# TUDSSL_condenar__Hardware_PCBs_Logger_Sc.net
KiCad netlist of a schematic drawn in Altium Designer
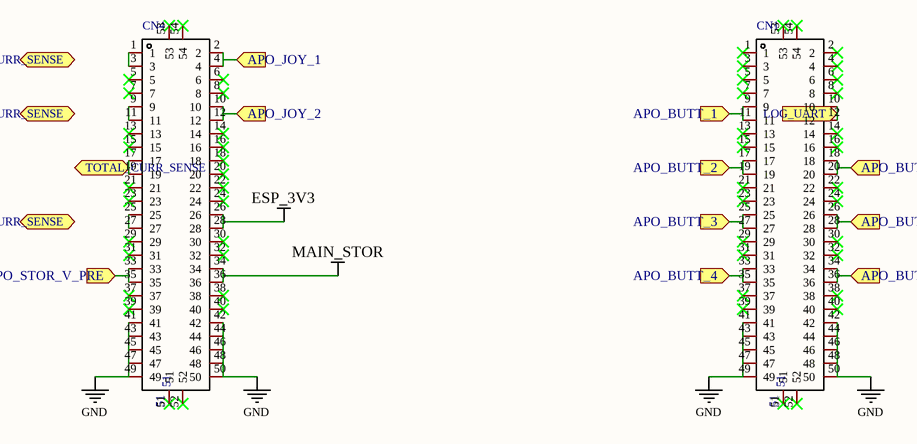
[diagram p0: TUDSSL_condenar__Hardware_PCBs_Logger_Schematic2__1_Connector.schdoc]

(export (version "E")
  (design (tool "Eeschema 10.0.6"))
  (components
    (comp (ref "CN1")
      (value "DF40C-50DP-0.4V(51)")
      (fields (field (name "MANUFACTURER") "HRS(广濑)") (field (name "NAME") "51") (field (name "NUMBER") "51"))
      (libsource (lib "altium-import") (part "root_0_DF40C-50DP-0.4V(51)_"))
    )
    (comp (ref "CN4")
      (value "DF40C-50DP-0.4V(51)")
      (fields (field (name "MANUFACTURER") "HRS(广濑)") (field (name "NAME") "51") (field (name "NUMBER") "51"))
      (libsource (lib "altium-import") (part "root_0_DF40C-50DP-0.4V(51)_"))
    )
  )
  (nets
    (net (code "1") (name "/APO_BUTT_1") (class "Default")
      (node (ref "CN1") (pin "11") (pinfunction "11_11") (pintype "passive"))
      (node (ref "CN1") (pin "9") (pinfunction "9_9") (pintype "passive"))
    )
    (net (code "2") (name "/APO_BUTT_2") (class "Default")
      (node (ref "CN1") (pin "17") (pinfunction "17_17") (pintype "passive"))
      (node (ref "CN1") (pin "19") (pinfunction "19_19") (pintype "passive"))
    )
    (net (code "3") (name "/APO_BUTT_3") (class "Default")
      (node (ref "CN1") (pin "25") (pinfunction "25_25") (pintype "passive"))
      (node (ref "CN1") (pin "27") (pinfunction "27_27") (pintype "passive"))
    )
    (net (code "4") (name "/APO_BUTT_4") (class "Default")
      (node (ref "CN1") (pin "33") (pinfunction "33_33") (pintype "passive"))
      (node (ref "CN1") (pin "35") (pinfunction "35_35") (pintype "passive"))
    )
    (net (code "5") (name "/APO_BUTT_5") (class "Default")
      (node (ref "CN1") (pin "34") (pinfunction "34_34") (pintype "passive"))
      (node (ref "CN1") (pin "36") (pinfunction "36_36") (pintype "passive"))
    )
    (net (code "6") (name "/APO_BUTT_6") (class "Default")
      (node (ref "CN1") (pin "26") (pinfunction "26_26") (pintype "passive"))
      (node (ref "CN1") (pin "28") (pinfunction "28_28") (pintype "passive"))
    )
    (net (code "7") (name "/APO_BUTT_7") (class "Default")
      (node (ref "CN1") (pin "18") (pinfunction "18_18") (pintype "passive"))
      (node (ref "CN1") (pin "20") (pinfunction "20_20") (pintype "passive"))
    )
    (net (code "8") (name "/APO_JOY_1") (class "Default")
      (node (ref "CN4") (pin "2") (pinfunction "2_2") (pintype "passive"))
      (node (ref "CN4") (pin "4") (pinfunction "4_4") (pintype "passive"))
    )
    (net (code "9") (name "/APO_JOY_2") (class "Default")
      (node (ref "CN4") (pin "10") (pinfunction "10_10") (pintype "passive"))
      (node (ref "CN4") (pin "12") (pinfunction "12_12") (pintype "passive"))
    )
    (net (code "10") (name "/APO_STOR_V_PRE") (class "Default")
      (node (ref "CN4") (pin "33") (pinfunction "33_33") (pintype "passive"))
      (node (ref "CN4") (pin "35") (pinfunction "35_35") (pintype "passive"))
    )
    (net (code "13") (name "/LOG_UART") (class "Default")
      (node (ref "CN1") (pin "10") (pinfunction "10_10") (pintype "passive"))
      (node (ref "CN1") (pin "12") (pinfunction "12_12") (pintype "passive"))
    )
    (net (code "16") (name "ESP_3V3") (class "Default")
      (node (ref "CN4") (pin "26") (pinfunction "26_26") (pintype "passive"))
      (node (ref "CN4") (pin "28") (pinfunction "28_28") (pintype "passive"))
    )
    (net (code "17") (name "GND") (class "Default")
      (node (ref "CN1") (pin "41") (pinfunction "41_41") (pintype "passive"))
      (node (ref "CN1") (pin "42") (pinfunction "42_42") (pintype "passive"))
      (node (ref "CN1") (pin "43") (pinfunction "43_43") (pintype "passive"))
      (node (ref "CN1") (pin "44") (pinfunction "44_44") (pintype "passive"))
      (node (ref "CN1") (pin "45") (pinfunction "45_45") (pintype "passive"))
      (node (ref "CN1") (pin "46") (pinfunction "46_46") (pintype "passive"))
      (node (ref "CN1") (pin "47") (pinfunction "47_47") (pintype "passive"))
      (node (ref "CN1") (pin "48") (pinfunction "48_48") (pintype "passive"))
      (node (ref "CN1") (pin "49") (pinfunction "49_49") (pintype "passive"))
      (node (ref "CN1") (pin "50") (pinfunction "50_50") (pintype "passive"))
      (node (ref "CN4") (pin "41") (pinfunction "41_41") (pintype "passive"))
      (node (ref "CN4") (pin "42") (pinfunction "42_42") (pintype "passive"))
      (node (ref "CN4") (pin "43") (pinfunction "43_43") (pintype "passive"))
      (node (ref "CN4") (pin "44") (pinfunction "44_44") (pintype "passive"))
      (node (ref "CN4") (pin "45") (pinfunction "45_45") (pintype "passive"))
      (node (ref "CN4") (pin "46") (pinfunction "46_46") (pintype "passive"))
      (node (ref "CN4") (pin "47") (pinfunction "47_47") (pintype "passive"))
      (node (ref "CN4") (pin "48") (pinfunction "48_48") (pintype "passive"))
      (node (ref "CN4") (pin "49") (pinfunction "49_49") (pintype "passive"))
      (node (ref "CN4") (pin "50") (pinfunction "50_50") (pintype "passive"))
    )
    (net (code "18") (name "MAIN_STOR") (class "Default")
      (node (ref "CN4") (pin "34") (pinfunction "34_34") (pintype "passive"))
      (node (ref "CN4") (pin "36") (pinfunction "36_36") (pintype "passive"))
    )
    (net (code "19") (name "Net-(CN4-Pad1)") (class "Default")
      (node (ref "CN4") (pin "1") (pinfunction "1_1") (pintype "passive"))
      (node (ref "CN4") (pin "3") (pinfunction "3_3") (pintype "passive"))
    )
    (net (code "20") (name "Net-(CN4-Pad11)") (class "Default")
      (node (ref "CN4") (pin "11") (pinfunction "11_11") (pintype "passive"))
      (node (ref "CN4") (pin "9") (pinfunction "9_9") (pintype "passive"))
    )
    (net (code "21") (name "Net-(CN4-Pad17)") (class "Default")
      (node (ref "CN4") (pin "17") (pinfunction "17_17") (pintype "passive"))
      (node (ref "CN4") (pin "19") (pinfunction "19_19") (pintype "passive"))
    )
    (net (code "22") (name "Net-(CN4-Pad25)") (class "Default")
      (node (ref "CN4") (pin "25") (pinfunction "25_25") (pintype "passive"))
      (node (ref "CN4") (pin "27") (pinfunction "27_27") (pintype "passive"))
    )
    (net (code "23") (name "unconnected-(CN1-Pad1)") (class "Default")
      (node (ref "CN1") (pin "1") (pinfunction "1_1") (pintype "passive+no_connect"))
    )
    (net (code "24") (name "unconnected-(CN1-Pad2)") (class "Default")
      (node (ref "CN1") (pin "2") (pinfunction "2_2") (pintype "passive+no_connect"))
    )
    (net (code "25") (name "unconnected-(CN1-Pad3)") (class "Default")
      (node (ref "CN1") (pin "3") (pinfunction "3_3") (pintype "passive+no_connect"))
    )
    (net (code "26") (name "unconnected-(CN1-Pad4)") (class "Default")
      (node (ref "CN1") (pin "4") (pinfunction "4_4") (pintype "passive+no_connect"))
    )
    (net (code "27") (name "unconnected-(CN1-Pad5)") (class "Default")
      (node (ref "CN1") (pin "5") (pinfunction "5_5") (pintype "passive+no_connect"))
    )
    (net (code "28") (name "unconnected-(CN1-Pad6)") (class "Default")
      (node (ref "CN1") (pin "6") (pinfunction "6_6") (pintype "passive+no_connect"))
    )
    (net (code "29") (name "unconnected-(CN1-Pad7)") (class "Default")
      (node (ref "CN1") (pin "7") (pinfunction "7_7") (pintype "passive+no_connect"))
    )
    (net (code "30") (name "unconnected-(CN1-Pad8)") (class "Default")
      (node (ref "CN1") (pin "8") (pinfunction "8_8") (pintype "passive+no_connect"))
    )
    (net (code "31") (name "unconnected-(CN1-Pad13)") (class "Default")
      (node (ref "CN1") (pin "13") (pinfunction "13_13") (pintype "passive+no_connect"))
    )
    (net (code "32") (name "unconnected-(CN1-Pad14)") (class "Default")
      (node (ref "CN1") (pin "14") (pinfunction "14_14") (pintype "passive+no_connect"))
    )
    (net (code "33") (name "unconnected-(CN1-Pad15)") (class "Default")
      (node (ref "CN1") (pin "15") (pinfunction "15_15") (pintype "passive+no_connect"))
    )
    (net (code "34") (name "unconnected-(CN1-Pad16)") (class "Default")
      (node (ref "CN1") (pin "16") (pinfunction "16_16") (pintype "passive+no_connect"))
    )
    (net (code "35") (name "unconnected-(CN1-Pad21)") (class "Default")
      (node (ref "CN1") (pin "21") (pinfunction "21_21") (pintype "passive+no_connect"))
    )
    (net (code "36") (name "unconnected-(CN1-Pad22)") (class "Default")
      (node (ref "CN1") (pin "22") (pinfunction "22_22") (pintype "passive+no_connect"))
    )
    (net (code "37") (name "unconnected-(CN1-Pad23)") (class "Default")
      (node (ref "CN1") (pin "23") (pinfunction "23_23") (pintype "passive+no_connect"))
    )
    (net (code "38") (name "unconnected-(CN1-Pad24)") (class "Default")
      (node (ref "CN1") (pin "24") (pinfunction "24_24") (pintype "passive+no_connect"))
    )
    (net (code "39") (name "unconnected-(CN1-Pad29)") (class "Default")
      (node (ref "CN1") (pin "29") (pinfunction "29_29") (pintype "passive+no_connect"))
    )
    (net (code "40") (name "unconnected-(CN1-Pad30)") (class "Default")
      (node (ref "CN1") (pin "30") (pinfunction "30_30") (pintype "passive+no_connect"))
    )
    (net (code "41") (name "unconnected-(CN1-Pad31)") (class "Default")
      (node (ref "CN1") (pin "31") (pinfunction "31_31") (pintype "passive+no_connect"))
    )
    (net (code "42") (name "unconnected-(CN1-Pad32)") (class "Default")
      (node (ref "CN1") (pin "32") (pinfunction "32_32") (pintype "passive+no_connect"))
    )
    (net (code "43") (name "unconnected-(CN1-Pad37)") (class "Default")
      (node (ref "CN1") (pin "37") (pinfunction "37_37") (pintype "passive+no_connect"))
    )
    (net (code "44") (name "unconnected-(CN1-Pad38)") (class "Default")
      (node (ref "CN1") (pin "38") (pinfunction "38_38") (pintype "passive+no_connect"))
    )
    (net (code "45") (name "unconnected-(CN1-Pad39)") (class "Default")
      (node (ref "CN1") (pin "39") (pinfunction "39_39") (pintype "passive+no_connect"))
    )
    (net (code "46") (name "unconnected-(CN1-Pad40)") (class "Default")
      (node (ref "CN1") (pin "40") (pinfunction "40_40") (pintype "passive+no_connect"))
    )
    (net (code "47") (name "unconnected-(CN1-Pad51)") (class "Default")
      (node (ref "CN1") (pin "51") (pinfunction "51_51") (pintype "passive+no_connect"))
    )
    (net (code "48") (name "unconnected-(CN1-Pad52)") (class "Default")
      (node (ref "CN1") (pin "52") (pinfunction "52_52") (pintype "passive+no_connect"))
    )
    (net (code "49") (name "unconnected-(CN1-Pad53)") (class "Default")
      (node (ref "CN1") (pin "53") (pinfunction "53_53") (pintype "passive+no_connect"))
    )
    (net (code "50") (name "unconnected-(CN1-Pad54)") (class "Default")
      (node (ref "CN1") (pin "54") (pinfunction "54_54") (pintype "passive+no_connect"))
    )
    (net (code "51") (name "unconnected-(CN4-Pad5)") (class "Default")
      (node (ref "CN4") (pin "5") (pinfunction "5_5") (pintype "passive+no_connect"))
    )
    (net (code "52") (name "unconnected-(CN4-Pad6)") (class "Default")
      (node (ref "CN4") (pin "6") (pinfunction "6_6") (pintype "passive+no_connect"))
    )
    (net (code "53") (name "unconnected-(CN4-Pad7)") (class "Default")
      (node (ref "CN4") (pin "7") (pinfunction "7_7") (pintype "passive+no_connect"))
    )
    (net (code "54") (name "unconnected-(CN4-Pad8)") (class "Default")
      (node (ref "CN4") (pin "8") (pinfunction "8_8") (pintype "passive+no_connect"))
    )
    (net (code "55") (name "unconnected-(CN4-Pad13)") (class "Default")
      (node (ref "CN4") (pin "13") (pinfunction "13_13") (pintype "passive+no_connect"))
    )
    (net (code "56") (name "unconnected-(CN4-Pad14)") (class "Default")
      (node (ref "CN4") (pin "14") (pinfunction "14_14") (pintype "passive+no_connect"))
    )
    (net (code "57") (name "unconnected-(CN4-Pad15)") (class "Default")
      (node (ref "CN4") (pin "15") (pinfunction "15_15") (pintype "passive+no_connect"))
    )
    (net (code "58") (name "unconnected-(CN4-Pad16)") (class "Default")
      (node (ref "CN4") (pin "16") (pinfunction "16_16") (pintype "passive+no_connect"))
    )
    (net (code "59") (name "unconnected-(CN4-Pad18)") (class "Default")
      (node (ref "CN4") (pin "18") (pinfunction "18_18") (pintype "passive+no_connect"))
    )
    (net (code "60") (name "unconnected-(CN4-Pad20)") (class "Default")
      (node (ref "CN4") (pin "20") (pinfunction "20_20") (pintype "passive+no_connect"))
    )
    (net (code "61") (name "unconnected-(CN4-Pad21)") (class "Default")
      (node (ref "CN4") (pin "21") (pinfunction "21_21") (pintype "passive+no_connect"))
    )
    (net (code "62") (name "unconnected-(CN4-Pad22)") (class "Default")
      (node (ref "CN4") (pin "22") (pinfunction "22_22") (pintype "passive+no_connect"))
    )
    (net (code "63") (name "unconnected-(CN4-Pad23)") (class "Default")
      (node (ref "CN4") (pin "23") (pinfunction "23_23") (pintype "passive+no_connect"))
    )
    (net (code "64") (name "unconnected-(CN4-Pad24)") (class "Default")
      (node (ref "CN4") (pin "24") (pinfunction "24_24") (pintype "passive+no_connect"))
    )
    (net (code "65") (name "unconnected-(CN4-Pad29)") (class "Default")
      (node (ref "CN4") (pin "29") (pinfunction "29_29") (pintype "passive+no_connect"))
    )
    (net (code "66") (name "unconnected-(CN4-Pad30)") (class "Default")
      (node (ref "CN4") (pin "30") (pinfunction "30_30") (pintype "passive+no_connect"))
    )
    (net (code "67") (name "unconnected-(CN4-Pad31)") (class "Default")
      (node (ref "CN4") (pin "31") (pinfunction "31_31") (pintype "passive+no_connect"))
    )
    (net (code "68") (name "unconnected-(CN4-Pad32)") (class "Default")
      (node (ref "CN4") (pin "32") (pinfunction "32_32") (pintype "passive+no_connect"))
    )
    (net (code "69") (name "unconnected-(CN4-Pad37)") (class "Default")
      (node (ref "CN4") (pin "37") (pinfunction "37_37") (pintype "passive+no_connect"))
    )
    (net (code "70") (name "unconnected-(CN4-Pad38)") (class "Default")
      (node (ref "CN4") (pin "38") (pinfunction "38_38") (pintype "passive+no_connect"))
    )
    (net (code "71") (name "unconnected-(CN4-Pad39)") (class "Default")
      (node (ref "CN4") (pin "39") (pinfunction "39_39") (pintype "passive+no_connect"))
    )
    (net (code "72") (name "unconnected-(CN4-Pad40)") (class "Default")
      (node (ref "CN4") (pin "40") (pinfunction "40_40") (pintype "passive+no_connect"))
    )
    (net (code "73") (name "unconnected-(CN4-Pad51)") (class "Default")
      (node (ref "CN4") (pin "51") (pinfunction "51_51") (pintype "passive+no_connect"))
    )
    (net (code "74") (name "unconnected-(CN4-Pad52)") (class "Default")
      (node (ref "CN4") (pin "52") (pinfunction "52_52") (pintype "passive+no_connect"))
    )
    (net (code "75") (name "unconnected-(CN4-Pad53)") (class "Default")
      (node (ref "CN4") (pin "53") (pinfunction "53_53") (pintype "passive+no_connect"))
    )
    (net (code "76") (name "unconnected-(CN4-Pad54)") (class "Default")
      (node (ref "CN4") (pin "54") (pinfunction "54_54") (pintype "passive+no_connect"))
    )
  )
)
